# P-MT3620RDB-PS-1-0.net
KiCad netlist of a schematic drawn in Altium Designer
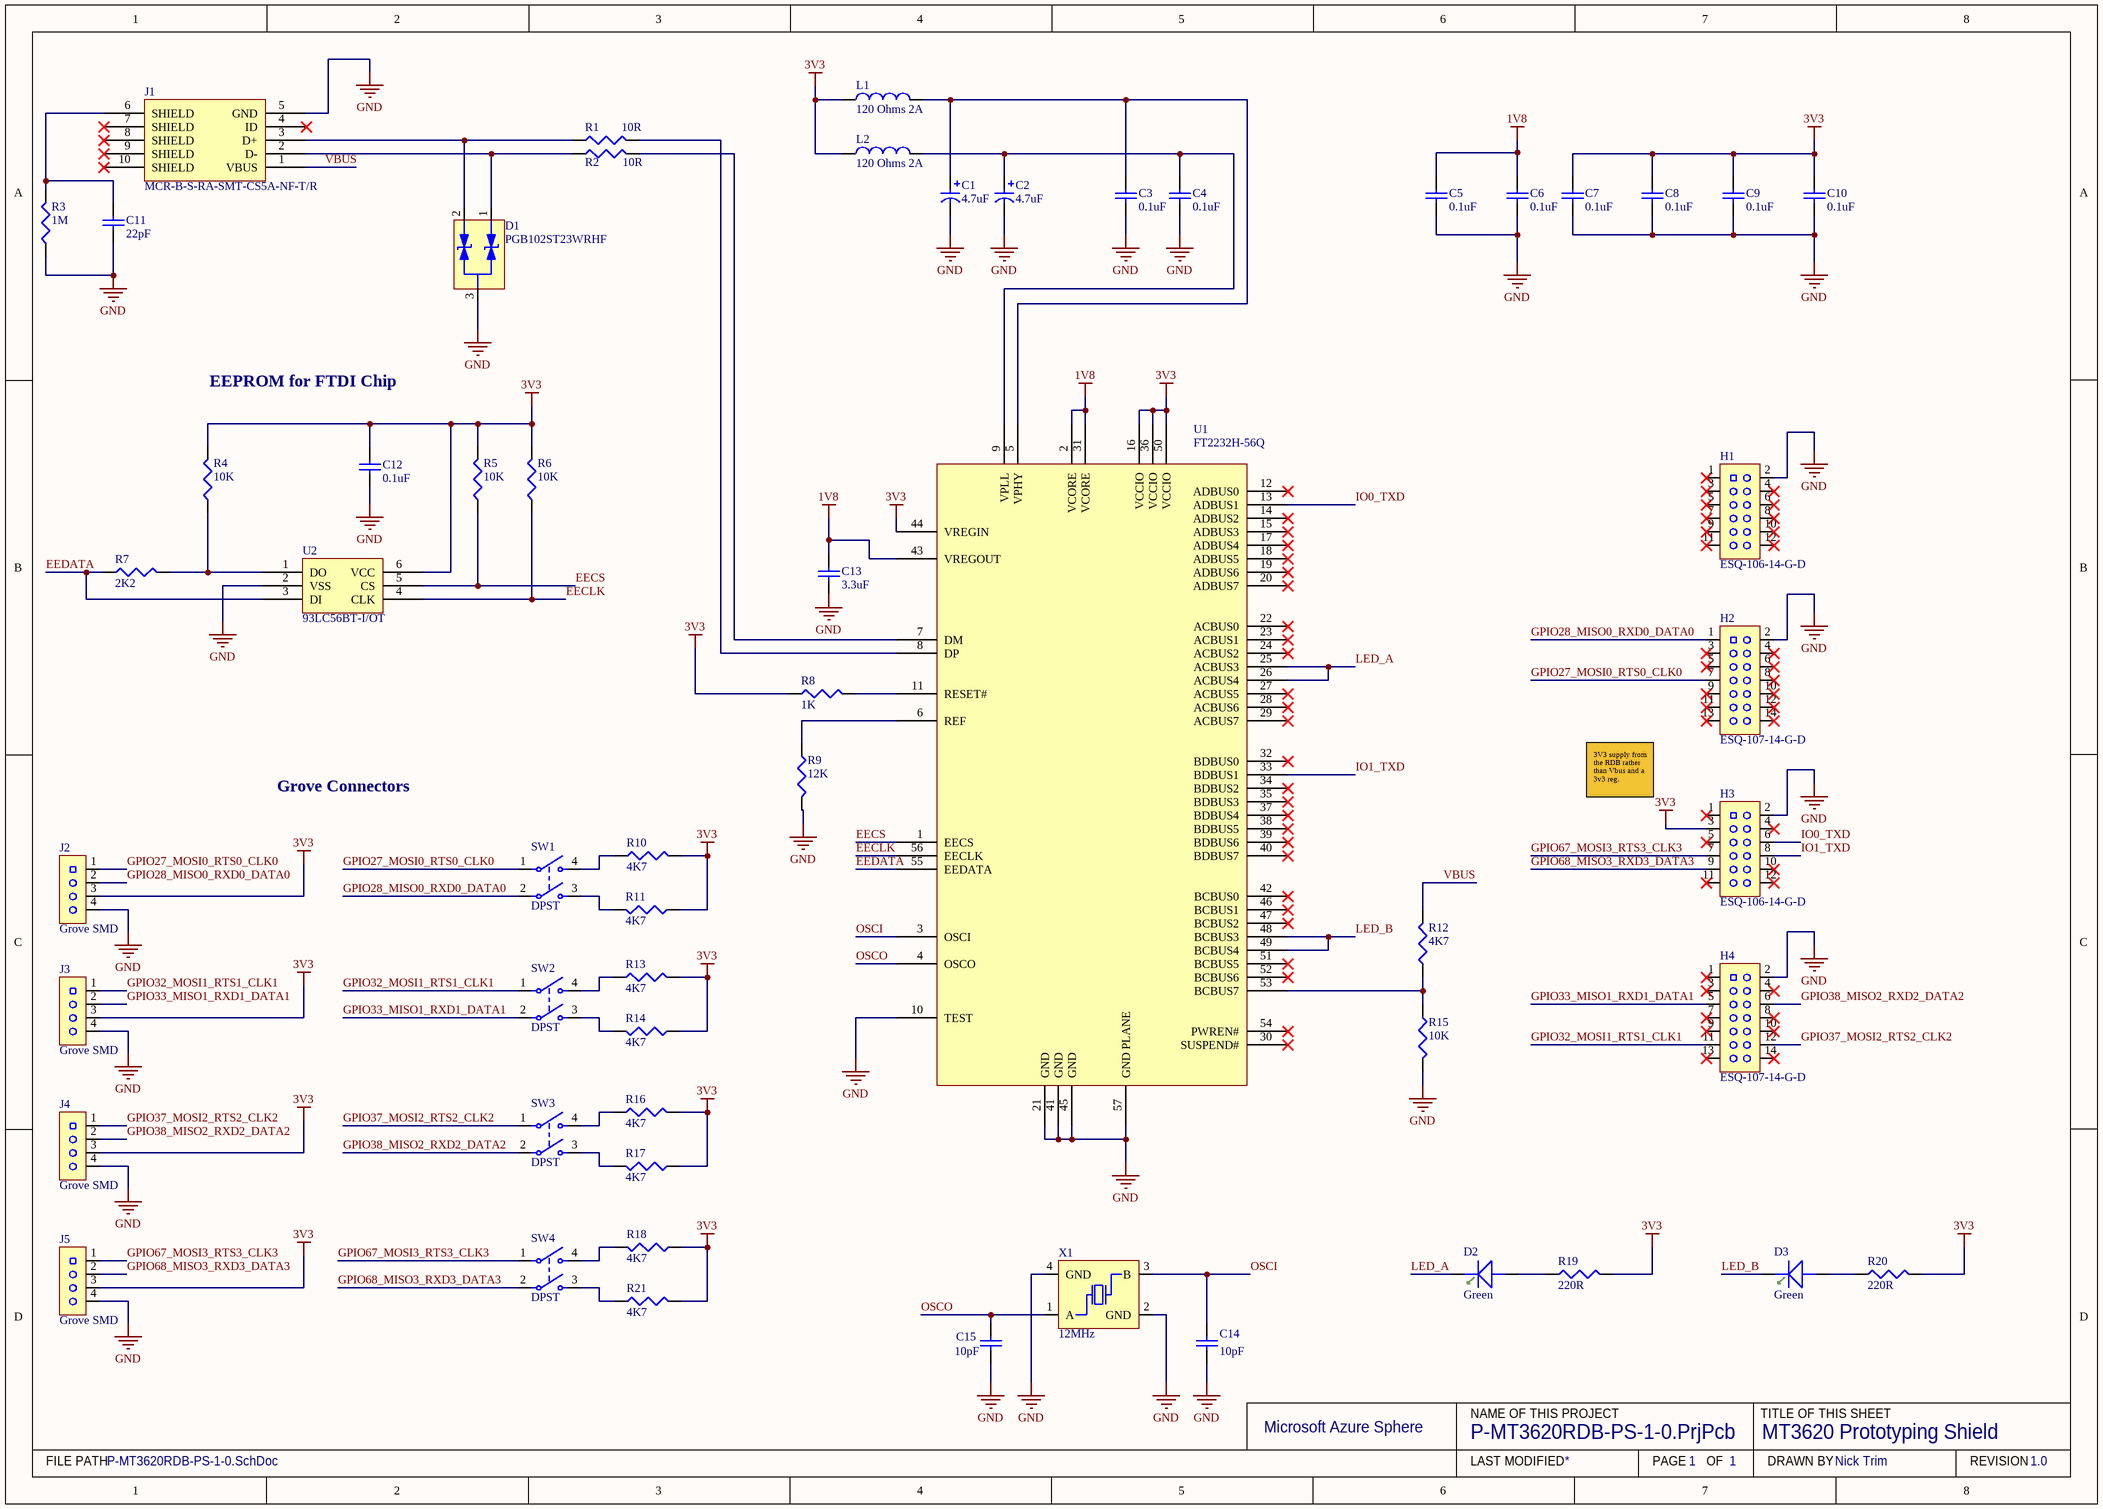
[diagram p0: P-MT3620RDB-PS-1-0.SchDoc]

(export (version "E")
  (design (tool "Eeschema 10.0.6"))
  (components
    (comp (ref "C1")
      (value "4.7uF")
      (footprint "C0603_TANT")
      (fields
        (field (name "MANUFACTURER") "Kyocera AVX")
        (field (name "MANUFACTURER PART NUMBER") "F981A475MMA")
        (field (name "TOLERANCE") "20%")
      )
      (libsource (lib "Prototyping Shield") (part "F981A475MMA"))
    )
    (comp (ref "C2")
      (value "4.7uF")
      (footprint "C0603_TANT")
      (fields
        (field (name "MANUFACTURER") "Kyocera AVX")
        (field (name "MANUFACTURER PART NUMBER") "F981A475MMA")
        (field (name "TOLERANCE") "20%")
      )
      (libsource (lib "Prototyping Shield") (part "F981A475MMA"))
    )
    (comp (ref "C3")
      (value "0.1uF")
      (footprint "C0603")
      (description "CL10 Series 0603 0.1 uF 50 V ±10% Tolerance X7R Multilayer Ceramic Capacitor")
      (fields
        (field (name "MANUFACTURER") "Samsung")
        (field (name "MANUFACTURER PART NUMBER") "CL10B104KB8NNNL")
      )
      (libsource (lib "Prototyping Shield") (part "CL10B104KB8NNNL"))
    )
    (comp (ref "C4")
      (value "0.1uF")
      (footprint "C0603")
      (description "CL10 Series 0603 0.1 uF 50 V ±10% Tolerance X7R Multilayer Ceramic Capacitor")
      (fields
        (field (name "MANUFACTURER") "Samsung")
        (field (name "MANUFACTURER PART NUMBER") "CL10B104KB8NNNL")
      )
      (libsource (lib "Prototyping Shield") (part "CL10B104KB8NNNL"))
    )
    (comp (ref "C5")
      (value "0.1uF")
      (footprint "C0603")
      (description "CL10 Series 0603 0.1 uF 50 V ±10% Tolerance X7R Multilayer Ceramic Capacitor")
      (fields
        (field (name "MANUFACTURER") "Samsung")
        (field (name "MANUFACTURER PART NUMBER") "CL10B104KB8NNNL")
      )
      (libsource (lib "Prototyping Shield") (part "CL10B104KB8NNNL"))
    )
    (comp (ref "C6")
      (value "0.1uF")
      (footprint "C0603")
      (description "CL10 Series 0603 0.1 uF 50 V ±10% Tolerance X7R Multilayer Ceramic Capacitor")
      (fields
        (field (name "MANUFACTURER") "Samsung")
        (field (name "MANUFACTURER PART NUMBER") "CL10B104KB8NNNL")
      )
      (libsource (lib "Prototyping Shield") (part "CL10B104KB8NNNL"))
    )
    (comp (ref "C7")
      (value "0.1uF")
      (footprint "C0603")
      (description "CL10 Series 0603 0.1 uF 50 V ±10% Tolerance X7R Multilayer Ceramic Capacitor")
      (fields
        (field (name "MANUFACTURER") "Samsung")
        (field (name "MANUFACTURER PART NUMBER") "CL10B104KB8NNNL")
      )
      (libsource (lib "Prototyping Shield") (part "CL10B104KB8NNNL"))
    )
    (comp (ref "C8")
      (value "0.1uF")
      (footprint "C0603")
      (description "CL10 Series 0603 0.1 uF 50 V ±10% Tolerance X7R Multilayer Ceramic Capacitor")
      (fields
        (field (name "MANUFACTURER") "Samsung")
        (field (name "MANUFACTURER PART NUMBER") "CL10B104KB8NNNL")
      )
      (libsource (lib "Prototyping Shield") (part "CL10B104KB8NNNL"))
    )
    (comp (ref "C9")
      (value "0.1uF")
      (footprint "C0603")
      (description "CL10 Series 0603 0.1 uF 50 V ±10% Tolerance X7R Multilayer Ceramic Capacitor")
      (fields
        (field (name "MANUFACTURER") "Samsung")
        (field (name "MANUFACTURER PART NUMBER") "CL10B104KB8NNNL")
      )
      (libsource (lib "Prototyping Shield") (part "CL10B104KB8NNNL"))
    )
    (comp (ref "C10")
      (value "0.1uF")
      (footprint "C0603")
      (description "CL10 Series 0603 0.1 uF 50 V ±10% Tolerance X7R Multilayer Ceramic Capacitor")
      (fields
        (field (name "MANUFACTURER") "Samsung")
        (field (name "MANUFACTURER PART NUMBER") "CL10B104KB8NNNL")
      )
      (libsource (lib "Schlib1") (part "CL10B104KB8NNNL"))
    )
    (comp (ref "C11")
      (value "22pF")
      (footprint "C0603")
      (description "Cap Ceramic 22pF 50VDC C0G 5% SMD 0603 Paper T/R")
      (fields
        (field (name "MANUFACTURER") "Yageo")
        (field (name "MANUFACTURER PART NUMBER") "CC0603JRNPO9BN220")
      )
      (libsource (lib "Prototyping Shield") (part "CC0603JRNPO9BN220"))
    )
    (comp (ref "C12")
      (value "0.1uF")
      (footprint "C0603")
      (description "CL10 Series 0603 0.1 uF 50 V ±10% Tolerance X7R Multilayer Ceramic Capacitor")
      (fields
        (field (name "MANUFACTURER") "Samsung")
        (field (name "MANUFACTURER PART NUMBER") "CL10B104KB8NNNL")
      )
      (libsource (lib "Prototyping Shield") (part "CL10B104KB8NNNL"))
    )
    (comp (ref "C13")
      (value "3.3uF")
      (footprint "C0603")
      (description "CAP CER 3.3UF 10V X5R 0603")
      (fields
        (field (name "MANUFACTURER") "Samsung")
        (field (name "MANUFACTURER PART NUMBER") "CL10A335KP8NNNC")
      )
      (libsource (lib "Prototyping Shield") (part "CL10A335KP8NNNC"))
    )
    (comp (ref "C14")
      (value "10pF")
      (footprint "C0603")
      (description "Cap Cer 10PF 100V Npo 0603")
      (fields
        (field (name "MANUFACTURER") "Yageo")
        (field (name "MANUFACTURER PART NUMBER") "CC0603FRNPO0BN100")
      )
      (libsource (lib "Prototyping Shield") (part "CC0603FRNPO0BN100"))
    )
    (comp (ref "C15")
      (value "10pF")
      (footprint "C0603")
      (description "Cap Cer 10PF 100V Npo 0603")
      (fields
        (field (name "MANUFACTURER") "Yageo")
        (field (name "MANUFACTURER PART NUMBER") "CC0603FRNPO0BN100")
      )
      (libsource (lib "Prototyping Shield") (part "CC0603FRNPO0BN100"))
    )
    (comp (ref "D1")
      (value "PGB102ST23WRHF")
      (footprint "SOT95P245X110-3N")
      (description "Tvs Diode 24V 150V SOT23-3")
      (fields (field (name "MANUFACTURER") "Littelfuse"))
      (libsource (lib "Schlib1") (part "PGB102ST23WRHF"))
    )
    (comp (ref "D2")
      (value "Green")
      (footprint "Rohm SML-D12 Green")
      (description "ROHM - SML-D12P8WT86 - LED, EXCELED, Green, SMD, 0603, 20 mA, 2.2 V, 560 nm")
      (fields (field (name "MANUFACTURER") "Rohm") (field (name "MANUFACTURER PART NUMBER") "SML-D12P8WT86"))
      (libsource (lib "Prototyping Shield") (part "SML-D12P8WT86"))
    )
    (comp (ref "D3")
      (value "Green")
      (footprint "Rohm SML-D12 Green")
      (description "ROHM - SML-D12P8WT86 - LED, EXCELED, Green, SMD, 0603, 20 mA, 2.2 V, 560 nm")
      (fields (field (name "MANUFACTURER") "Rohm") (field (name "MANUFACTURER PART NUMBER") "SML-D12P8WT86"))
      (libsource (lib "Prototyping Shield") (part "SML-D12P8WT86"))
    )
    (comp (ref "H1")
      (value "ESQ-106-14-G-D")
      (footprint "ESQ-106")
      (description "Conn Elevated Socket SKT 12 POS 2.54mm Solder ST Thru-Hole Tube")
      (fields (field (name "MANUFACTURER") "Samtec"))
      (libsource (lib "Schlib1") (part "ESQ-106-14-G-D"))
    )
    (comp (ref "H2")
      (value "ESQ-107-14-G-D")
      (footprint "ESQ-107")
      (fields (field (name "MANUFACTURER") "Samtec"))
      (libsource (lib "Schlib1") (part "ESQ-107-14-G-D"))
    )
    (comp (ref "H3")
      (value "ESQ-106-14-G-D")
      (footprint "ESQ-106")
      (description "Conn Elevated Socket SKT 12 POS 2.54mm Solder ST Thru-Hole Tube")
      (fields (field (name "MANUFACTURER") "Samtec"))
      (libsource (lib "Schlib1") (part "ESQ-106-14-G-D"))
    )
    (comp (ref "H4")
      (value "ESQ-107-14-G-D")
      (footprint "ESQ-107")
      (fields (field (name "MANUFACTURER") "Samtec"))
      (libsource (lib "Schlib1") (part "ESQ-107-14-G-D"))
    )
    (comp (ref "J1")
      (value "MCR-B-S-RA-SMT-CS5A-NF-T/R")
      (footprint "MCR-B-S-RA-SMT-CS5-T/R")
      (fields (field (name "MANUFACTURER") "Adam Equipment"))
      (libsource (lib "Prototyping Shield") (part "MCR-B-S-RA-SMT-CS5A-NF-T/R"))
    )
    (comp (ref "J2")
      (value "Grove SMD")
      (footprint "Grove way SMD")
      (fields
        (field (name "MANUFACTURER") "Seeed Studio")
        (field (name "MANUFACTURER PART NUMBER") "114020163")
      )
      (libsource (lib "Prototyping Shield") (part "114020163"))
    )
    (comp (ref "J3")
      (value "Grove SMD")
      (footprint "Grove way SMD")
      (fields
        (field (name "MANUFACTURER") "Seeed Studio")
        (field (name "MANUFACTURER PART NUMBER") "114020163")
      )
      (libsource (lib "Prototyping Shield") (part "114020163"))
    )
    (comp (ref "J4")
      (value "Grove SMD")
      (footprint "Grove way SMD")
      (fields
        (field (name "MANUFACTURER") "Seeed Studio")
        (field (name "MANUFACTURER PART NUMBER") "114020163")
      )
      (libsource (lib "Prototyping Shield") (part "114020163"))
    )
    (comp (ref "J5")
      (value "Grove SMD")
      (footprint "Grove way SMD")
      (fields
        (field (name "MANUFACTURER") "Seeed Studio")
        (field (name "MANUFACTURER PART NUMBER") "114020163")
      )
      (libsource (lib "Prototyping Shield") (part "114020163"))
    )
    (comp (ref "L1")
      (value "120 Ohms 2A")
      (footprint "0603 IND")
      (description "MURATA - BLM18PG121SN1D - FERRITE, BEAD, 0603, 0.05OHM, 2A")
      (fields
        (field (name "MANUFACTURER") "Murata")
        (field (name "MANUFACTURER PART NUMBER") "BLM18PG121SN1D")
      )
      (libsource (lib "Prototyping Shield") (part "BLM18PG121SN1D"))
    )
    (comp (ref "L2")
      (value "120 Ohms 2A")
      (footprint "0603 IND")
      (description "MURATA - BLM18PG121SN1D - FERRITE, BEAD, 0603, 0.05OHM, 2A")
      (fields
        (field (name "MANUFACTURER") "Murata")
        (field (name "MANUFACTURER PART NUMBER") "BLM18PG121SN1D")
      )
      (libsource (lib "Prototyping Shield") (part "BLM18PG121SN1D"))
    )
    (comp (ref "R1")
      (value "10R")
      (footprint "R0603")
      (description "YAGEO (PHYCOMP) - RC0603FR-0710RL - RES, THICK FILM, 10R, 1%, 0.1W, 0603")
      (fields
        (field (name "MANUFACTURER") "Yageo")
        (field (name "MANUFACTURER PART NUMBER") "RC0603FR-0710RL")
      )
      (libsource (lib "Schlib1") (part "RC0603FR-0710RL"))
    )
    (comp (ref "R2")
      (value "10R")
      (footprint "R0603")
      (description "YAGEO (PHYCOMP) - RC0603FR-0710RL - RES, THICK FILM, 10R, 1%, 0.1W, 0603")
      (fields
        (field (name "MANUFACTURER") "Yageo")
        (field (name "MANUFACTURER PART NUMBER") "RC0603FR-0710RL")
      )
      (libsource (lib "Schlib1") (part "RC0603FR-0710RL"))
    )
    (comp (ref "R3")
      (value "1M")
      (footprint "R0603")
      (description "RES SMD 1M OHM 1% 1/10W 0603")
      (fields
        (field (name "MANUFACTURER") "Yageo")
        (field (name "MANUFACTURER PART NUMBER") "AC0603FR-071ML")
      )
      (libsource (lib "Prototyping Shield") (part "AC0603FR-071ML"))
    )
    (comp (ref "R4")
      (value "10K")
      (footprint "R0603")
      (description "Res General Purpose Thick Film 0603 10K Ohm 1% 1/10W ±100ppm/°C Molded SMD Paper T/R")
      (fields
        (field (name "MANUFACTURER") "Yageo")
        (field (name "MANUFACTURER PART NUMBER") "RC0603FR-0710KL")
      )
      (libsource (lib "Prototyping Shield") (part "RC0603FR-0710KL"))
    )
    (comp (ref "R5")
      (value "10K")
      (footprint "R0603")
      (description "Res General Purpose Thick Film 0603 10K Ohm 1% 1/10W ±100ppm/°C Molded SMD Paper T/R")
      (fields
        (field (name "MANUFACTURER") "Yageo")
        (field (name "MANUFACTURER PART NUMBER") "RC0603FR-0710KL")
      )
      (libsource (lib "Prototyping Shield") (part "RC0603FR-0710KL"))
    )
    (comp (ref "R6")
      (value "10K")
      (footprint "R0603")
      (description "Res General Purpose Thick Film 0603 10K Ohm 1% 1/10W ±100ppm/°C Molded SMD Paper T/R")
      (fields
        (field (name "MANUFACTURER") "Yageo")
        (field (name "MANUFACTURER PART NUMBER") "RC0603FR-0710KL")
      )
      (libsource (lib "Prototyping Shield") (part "RC0603FR-0710KL"))
    )
    (comp (ref "R7")
      (value "2K2")
      (footprint "R0603")
      (description "YAGEO - RC0603FR-072K2L.. - RES, THICK FILM, 2K2, 1%, 0.1W, 0603")
      (fields
        (field (name "MANUFACTURER") "Yageo")
        (field (name "MANUFACTURER PART NUMBER") "RC0603FR-072K2L")
      )
      (libsource (lib "Prototyping Shield") (part "RC0603FR-072K2L"))
    )
    (comp (ref "R8")
      (value "1K")
      (footprint "R0603")
      (description "RES SMD 1K OHM 1% 1/10W 0603")
      (fields
        (field (name "MANUFACTURER") "Yageo")
        (field (name "MANUFACTURER PART NUMBER") "RC0603FR-071KL")
      )
      (libsource (lib "Prototyping Shield") (part "RC0603FR-071KL"))
    )
    (comp (ref "R9")
      (value "12K")
      (footprint "R0603")
      (fields
        (field (name "MANUFACTURER") "Yageo")
        (field (name "MANUFACTURER PART NUMBER") "RC0603FR-0712KL")
        (field (name "TOLERANCE") "1%")
      )
      (libsource (lib "Prototyping Shield") (part "RC0603FR-0712KL"))
    )
    (comp (ref "R10")
      (value "4K7")
      (footprint "R0603")
      (description "RES SMD 4.7K OHM 1% 1/10W 0603")
      (fields
        (field (name "MANUFACTURER") "Yageo")
        (field (name "MANUFACTURER PART NUMBER") "RC0603FR-074K7L")
      )
      (libsource (lib "Prototyping Shield") (part "RC0603FR-074K7L"))
    )
    (comp (ref "R11")
      (value "4K7")
      (footprint "R0603")
      (description "RES SMD 4.7K OHM 1% 1/10W 0603")
      (fields
        (field (name "MANUFACTURER") "Yageo")
        (field (name "MANUFACTURER PART NUMBER") "RC0603FR-074K7L")
      )
      (libsource (lib "Prototyping Shield") (part "RC0603FR-074K7L"))
    )
    (comp (ref "R12")
      (value "4K7")
      (footprint "R0603")
      (description "RES SMD 4.7K OHM 1% 1/10W 0603")
      (fields
        (field (name "MANUFACTURER") "Yageo")
        (field (name "MANUFACTURER PART NUMBER") "RC0603FR-074K7L")
      )
      (libsource (lib "Schlib1") (part "RC0603FR-074K7L"))
    )
    (comp (ref "R13")
      (value "4K7")
      (footprint "R0603")
      (description "RES SMD 4.7K OHM 1% 1/10W 0603")
      (fields
        (field (name "MANUFACTURER") "Yageo")
        (field (name "MANUFACTURER PART NUMBER") "RC0603FR-074K7L")
      )
      (libsource (lib "Prototyping Shield") (part "RC0603FR-074K7L"))
    )
    (comp (ref "R14")
      (value "4K7")
      (footprint "R0603")
      (description "RES SMD 4.7K OHM 1% 1/10W 0603")
      (fields
        (field (name "MANUFACTURER") "Yageo")
        (field (name "MANUFACTURER PART NUMBER") "RC0603FR-074K7L")
      )
      (libsource (lib "Prototyping Shield") (part "RC0603FR-074K7L"))
    )
    (comp (ref "R15")
      (value "10K")
      (footprint "R0603")
      (description "Res General Purpose Thick Film 0603 10K Ohm 1% 1/10W ±100ppm/°C Molded SMD Paper T/R")
      (fields
        (field (name "MANUFACTURER") "Yageo")
        (field (name "MANUFACTURER PART NUMBER") "RC0603FR-0710KL")
      )
      (libsource (lib "Schlib1") (part "RC0603FR-0710KL"))
    )
    (comp (ref "R16")
      (value "4K7")
      (footprint "R0603")
      (description "RES SMD 4.7K OHM 1% 1/10W 0603")
      (fields
        (field (name "MANUFACTURER") "Yageo")
        (field (name "MANUFACTURER PART NUMBER") "RC0603FR-074K7L")
      )
      (libsource (lib "Prototyping Shield") (part "RC0603FR-074K7L"))
    )
    (comp (ref "R17")
      (value "4K7")
      (footprint "R0603")
      (description "RES SMD 4.7K OHM 1% 1/10W 0603")
      (fields
        (field (name "MANUFACTURER") "Yageo")
        (field (name "MANUFACTURER PART NUMBER") "RC0603FR-074K7L")
      )
      (libsource (lib "Prototyping Shield") (part "RC0603FR-074K7L"))
    )
    (comp (ref "R18")
      (value "4K7")
      (footprint "R0603")
      (description "RES SMD 4.7K OHM 1% 1/10W 0603")
      (fields
        (field (name "MANUFACTURER") "Yageo")
        (field (name "MANUFACTURER PART NUMBER") "RC0603FR-074K7L")
      )
      (libsource (lib "Prototyping Shield") (part "RC0603FR-074K7L"))
    )
    (comp (ref "R19")
      (value "220R")
      (footprint "R0603")
      (fields
        (field (name "MANUFACTURER") "Yageo")
        (field (name "MANUFACTURER PART NUMBER") "RC0603FR-07220RL")
        (field (name "TOLERANCE") "1%")
      )
      (libsource (lib "Prototyping Shield") (part "RC0603FR-07220RL"))
    )
    (comp (ref "R20")
      (value "220R")
      (footprint "R0603")
      (fields
        (field (name "MANUFACTURER") "Yageo")
        (field (name "MANUFACTURER PART NUMBER") "RC0603FR-07220RL")
        (field (name "TOLERANCE") "1%")
      )
      (libsource (lib "Prototyping Shield") (part "RC0603FR-07220RL"))
    )
    (comp (ref "R21")
      (value "4K7")
      (footprint "R0603")
      (description "RES SMD 4.7K OHM 1% 1/10W 0603")
      (fields
        (field (name "MANUFACTURER") "Yageo")
        (field (name "MANUFACTURER PART NUMBER") "RC0603FR-074K7L")
      )
      (libsource (lib "Prototyping Shield") (part "RC0603FR-074K7L"))
    )
    (comp (ref "SW1")
      (value "DPST")
      (footprint "204-211ST")
      (description "SWITCH SLIDE DIP DPST 50MA 24V")
      (fields (field (name "MANUFACTURER") "CTS") (field (name "MANUFACTURER PART NUMBER") "204-211ST"))
      (libsource (lib "Prototyping Shield") (part "204-211ST"))
    )
    (comp (ref "SW2")
      (value "DPST")
      (footprint "204-211ST")
      (description "SWITCH SLIDE DIP DPST 50MA 24V")
      (fields (field (name "MANUFACTURER") "CTS") (field (name "MANUFACTURER PART NUMBER") "204-211ST"))
      (libsource (lib "Prototyping Shield") (part "204-211ST"))
    )
    (comp (ref "SW3")
      (value "DPST")
      (footprint "204-211ST")
      (description "SWITCH SLIDE DIP DPST 50MA 24V")
      (fields (field (name "MANUFACTURER") "CTS") (field (name "MANUFACTURER PART NUMBER") "204-211ST"))
      (libsource (lib "Prototyping Shield") (part "204-211ST"))
    )
    (comp (ref "SW4")
      (value "DPST")
      (footprint "204-211ST")
      (description "SWITCH SLIDE DIP DPST 50MA 24V")
      (fields (field (name "MANUFACTURER") "CTS") (field (name "MANUFACTURER PART NUMBER") "204-211ST"))
      (libsource (lib "Prototyping Shield") (part "204-211ST"))
    )
    (comp (ref "U1")
      (value "FT2232H-56Q")
      (footprint "FT2232H-56Q")
      (description "IC DUAL USB TO UART/FIFO 56VQFN")
      (fields
        (field (name "MANUFACTURER") "FTDI")
        (field (name "MANUFACTURER PART NUMBER") "FT2232H-56Q-TRAY")
      )
      (libsource (lib "Prototyping Shield") (part "FT2232H-56Q-TRAY"))
    )
    (comp (ref "U2")
      (value "93LC56BT-I/OT")
      (footprint "SOT23-93C56B")
      (description "MICROCHIP - 93LC56BT-I/OT. - 2K, 128 X 16, SERIAL EE, IND ROHS COMPLIANT: YES")
      (fields (field (name "MANUFACTURER") "Microchip"))
      (libsource (lib "Prototyping Shield") (part "93LC56BT-I/OT"))
    )
    (comp (ref "X1")
      (value "12MHz")
      (footprint "TXC8Z")
      (description "Crystal 12MHz ±30ppm (Tol) ±30ppm (Stability) 18pF FUND 150Ohm 4-Pin SMD T/R")
      (fields (field (name "MANUFACTURER") "TXC") (field (name "MANUFACTURER PART NUMBER") "8Z-12.000MAAJ-T"))
      (libsource (lib "Prototyping Shield") (part "8Z-12.000MAAJ-T"))
    )
  )
  (nets
    (net (code "1") (name "/EECLK") (class "Default")
      (node (ref "R6") (pin "1") (pinfunction "1_1") (pintype "passive"))
      (node (ref "U1") (pin "56") (pinfunction "EECLK_56") (pintype "passive"))
      (node (ref "U2") (pin "4") (pinfunction "CLK_4") (pintype "passive"))
    )
    (net (code "2") (name "/EECS") (class "Default")
      (node (ref "R5") (pin "1") (pinfunction "1_1") (pintype "passive"))
      (node (ref "U1") (pin "1") (pinfunction "EECS_1") (pintype "passive"))
      (node (ref "U2") (pin "5") (pinfunction "CS_5") (pintype "passive"))
    )
    (net (code "3") (name "/EEDATA") (class "Default")
      (node (ref "R7") (pin "1") (pinfunction "1_1") (pintype "passive"))
      (node (ref "U1") (pin "55") (pinfunction "EEDATA_55") (pintype "passive"))
      (node (ref "U2") (pin "3") (pinfunction "DI_3") (pintype "passive"))
    )
    (net (code "4") (name "/GPIO27_MOSI0_RTS0_CLK0") (class "Default")
      (node (ref "H2") (pin "7") (pintype "passive"))
      (node (ref "J2") (pin "1") (pintype "passive"))
      (node (ref "SW1") (pin "1") (pintype "passive"))
    )
    (net (code "5") (name "/GPIO28_MISO0_RXD0_DATA0") (class "Default")
      (node (ref "H2") (pin "1") (pintype "passive"))
      (node (ref "J2") (pin "2") (pintype "passive"))
      (node (ref "SW1") (pin "2") (pintype "passive"))
    )
    (net (code "6") (name "/GPIO32_MOSI1_RTS1_CLK1") (class "Default")
      (node (ref "H4") (pin "11") (pintype "passive"))
      (node (ref "J3") (pin "1") (pintype "passive"))
      (node (ref "SW2") (pin "1") (pintype "passive"))
    )
    (net (code "7") (name "/GPIO33_MISO1_RXD1_DATA1") (class "Default")
      (node (ref "H4") (pin "5") (pintype "passive"))
      (node (ref "J3") (pin "2") (pintype "passive"))
      (node (ref "SW2") (pin "2") (pintype "passive"))
    )
    (net (code "8") (name "/GPIO37_MOSI2_RTS2_CLK2") (class "Default")
      (node (ref "H4") (pin "12") (pintype "passive"))
      (node (ref "J4") (pin "1") (pintype "passive"))
      (node (ref "SW3") (pin "1") (pintype "passive"))
    )
    (net (code "9") (name "/GPIO38_MISO2_RXD2_DATA2") (class "Default")
      (node (ref "H4") (pin "6") (pintype "passive"))
      (node (ref "J4") (pin "2") (pintype "passive"))
      (node (ref "SW3") (pin "2") (pintype "passive"))
    )
    (net (code "10") (name "/GPIO67_MOSI3_RTS3_CLK3") (class "Default")
      (node (ref "H3") (pin "7") (pintype "passive"))
      (node (ref "J5") (pin "1") (pintype "passive"))
      (node (ref "SW4") (pin "1") (pintype "passive"))
    )
    (net (code "11") (name "/GPIO68_MISO3_RXD3_DATA3") (class "Default")
      (node (ref "H3") (pin "9") (pintype "passive"))
      (node (ref "J5") (pin "2") (pintype "passive"))
      (node (ref "SW4") (pin "2") (pintype "passive"))
    )
    (net (code "12") (name "/IO0_TXD") (class "Default")
      (node (ref "H3") (pin "6") (pintype "passive"))
      (node (ref "U1") (pin "13") (pinfunction "ADBUS1_13") (pintype "passive"))
    )
    (net (code "13") (name "/IO1_TXD") (class "Default")
      (node (ref "H3") (pin "8") (pintype "passive"))
      (node (ref "U1") (pin "33") (pinfunction "BDBUS1_33") (pintype "passive"))
    )
    (net (code "14") (name "/LED_A") (class "Default")
      (node (ref "D2") (pin "1") (pinfunction "1_1") (pintype "passive"))
      (node (ref "U1") (pin "25") (pinfunction "ACBUS3_25") (pintype "passive"))
      (node (ref "U1") (pin "26") (pinfunction "ACBUS4_26") (pintype "passive"))
    )
    (net (code "15") (name "/LED_B") (class "Default")
      (node (ref "D3") (pin "1") (pinfunction "1_1") (pintype "passive"))
      (node (ref "U1") (pin "48") (pinfunction "BCBUS3_48") (pintype "passive"))
      (node (ref "U1") (pin "49") (pinfunction "BCBUS4_49") (pintype "passive"))
    )
    (net (code "16") (name "/OSCI") (class "Default")
      (node (ref "C14") (pin "1") (pinfunction "1_1") (pintype "passive"))
      (node (ref "U1") (pin "3") (pinfunction "OSCI_3") (pintype "passive"))
      (node (ref "X1") (pin "3") (pinfunction "B_3") (pintype "passive"))
    )
    (net (code "17") (name "/OSCO") (class "Default")
      (node (ref "C15") (pin "1") (pinfunction "1_1") (pintype "passive"))
      (node (ref "U1") (pin "4") (pinfunction "OSCO_4") (pintype "passive"))
      (node (ref "X1") (pin "1") (pinfunction "A_1") (pintype "passive"))
    )
    (net (code "18") (name "/VBUS") (class "Default")
      (node (ref "J1") (pin "1") (pinfunction "VBUS_1") (pintype "passive"))
      (node (ref "R12") (pin "2") (pinfunction "2_2") (pintype "passive"))
    )
    (net (code "19") (name "1V8") (class "Default")
      (node (ref "C13") (pin "2") (pinfunction "2_2") (pintype "passive"))
      (node (ref "C5") (pin "2") (pinfunction "2_2") (pintype "passive"))
      (node (ref "C6") (pin "2") (pinfunction "2_2") (pintype "passive"))
      (node (ref "U1") (pin "2") (pinfunction "VCORE_2") (pintype "passive"))
      (node (ref "U1") (pin "31") (pinfunction "VCORE_31") (pintype "passive"))
      (node (ref "U1") (pin "43") (pinfunction "VREGOUT_43") (pintype "passive"))
    )
    (net (code "20") (name "3V3") (class "Default")
      (node (ref "C10") (pin "2") (pinfunction "2_2") (pintype "passive"))
      (node (ref "C12") (pin "2") (pinfunction "2_2") (pintype "passive"))
      (node (ref "C7") (pin "1") (pinfunction "1_1") (pintype "passive"))
      (node (ref "C8") (pin "2") (pinfunction "2_2") (pintype "passive"))
      (node (ref "C9") (pin "2") (pinfunction "2_2") (pintype "passive"))
      (node (ref "H3") (pin "3") (pintype "passive"))
      (node (ref "J2") (pin "3") (pintype "passive"))
      (node (ref "J3") (pin "3") (pintype "passive"))
      (node (ref "J4") (pin "3") (pintype "passive"))
      (node (ref "J5") (pin "3") (pintype "passive"))
      (node (ref "L1") (pin "1") (pinfunction "1_1") (pintype "passive"))
      (node (ref "L2") (pin "1") (pinfunction "1_1") (pintype "passive"))
      (node (ref "R10") (pin "2") (pinfunction "2_2") (pintype "passive"))
      (node (ref "R11") (pin "1") (pinfunction "1_1") (pintype "passive"))
      (node (ref "R13") (pin "2") (pinfunction "2_2") (pintype "passive"))
      (node (ref "R14") (pin "1") (pinfunction "1_1") (pintype "passive"))
      (node (ref "R16") (pin "2") (pinfunction "2_2") (pintype "passive"))
      (node (ref "R17") (pin "1") (pinfunction "1_1") (pintype "passive"))
      (node (ref "R18") (pin "1") (pinfunction "1_1") (pintype "passive"))
      (node (ref "R19") (pin "2") (pinfunction "2_2") (pintype "passive"))
      (node (ref "R20") (pin "2") (pinfunction "2_2") (pintype "passive"))
      (node (ref "R21") (pin "2") (pinfunction "2_2") (pintype "passive"))
      (node (ref "R4") (pin "2") (pinfunction "2_2") (pintype "passive"))
      (node (ref "R5") (pin "2") (pinfunction "2_2") (pintype "passive"))
      (node (ref "R6") (pin "2") (pinfunction "2_2") (pintype "passive"))
      (node (ref "R8") (pin "1") (pinfunction "1_1") (pintype "passive"))
      (node (ref "U1") (pin "16") (pinfunction "VCCIO_16") (pintype "passive"))
      (node (ref "U1") (pin "36") (pinfunction "VCCIO_36") (pintype "passive"))
      (node (ref "U1") (pin "44") (pinfunction "VREGIN_44") (pintype "passive"))
      (node (ref "U1") (pin "50") (pinfunction "VCCIO_50") (pintype "passive"))
      (node (ref "U2") (pin "6") (pinfunction "VCC_6") (pintype "passive"))
    )
    (net (code "21") (name "GND") (class "Default")
      (node (ref "C1") (pin "2") (pinfunction "2_2") (pintype "passive"))
      (node (ref "C10") (pin "1") (pinfunction "1_1") (pintype "passive"))
      (node (ref "C11") (pin "1") (pinfunction "1_1") (pintype "passive"))
      (node (ref "C12") (pin "1") (pinfunction "1_1") (pintype "passive"))
      (node (ref "C13") (pin "1") (pinfunction "1_1") (pintype "passive"))
      (node (ref "C14") (pin "2") (pinfunction "2_2") (pintype "passive"))
      (node (ref "C15") (pin "2") (pinfunction "2_2") (pintype "passive"))
      (node (ref "C2") (pin "2") (pinfunction "2_2") (pintype "passive"))
      (node (ref "C3") (pin "2") (pinfunction "2_2") (pintype "passive"))
      (node (ref "C4") (pin "1") (pinfunction "1_1") (pintype "passive"))
      (node (ref "C5") (pin "1") (pinfunction "1_1") (pintype "passive"))
      (node (ref "C6") (pin "1") (pinfunction "1_1") (pintype "passive"))
      (node (ref "C7") (pin "2") (pinfunction "2_2") (pintype "passive"))
      (node (ref "C8") (pin "1") (pinfunction "1_1") (pintype "passive"))
      (node (ref "C9") (pin "1") (pinfunction "1_1") (pintype "passive"))
      (node (ref "D1") (pin "3") (pinfunction "3_3") (pintype "passive"))
      (node (ref "H1") (pin "2") (pintype "passive"))
      (node (ref "H2") (pin "2") (pintype "passive"))
      (node (ref "H3") (pin "2") (pintype "passive"))
      (node (ref "H4") (pin "2") (pintype "passive"))
      (node (ref "J1") (pin "5") (pinfunction "GND_5") (pintype "passive"))
      (node (ref "J2") (pin "4") (pintype "passive"))
      (node (ref "J3") (pin "4") (pintype "passive"))
      (node (ref "J4") (pin "4") (pintype "passive"))
      (node (ref "J5") (pin "4") (pintype "passive"))
      (node (ref "R15") (pin "2") (pinfunction "2_2") (pintype "passive"))
      (node (ref "R3") (pin "1") (pinfunction "1_1") (pintype "passive"))
      (node (ref "R9") (pin "2") (pinfunction "2_2") (pintype "passive"))
      (node (ref "U1") (pin "10") (pinfunction "TEST_10") (pintype "passive"))
      (node (ref "U1") (pin "21") (pinfunction "GND_21") (pintype "passive"))
      (node (ref "U1") (pin "41") (pinfunction "GND_41") (pintype "passive"))
      (node (ref "U1") (pin "45") (pinfunction "GND_45") (pintype "passive"))
      (node (ref "U1") (pin "57") (pinfunction "GND_PLANE_57") (pintype "passive"))
      (node (ref "U2") (pin "2") (pinfunction "VSS_2") (pintype "passive"))
      (node (ref "X1") (pin "2") (pinfunction "GND_2") (pintype "passive"))
      (node (ref "X1") (pin "4") (pinfunction "GND_4") (pintype "passive"))
    )
    (net (code "22") (name "Net-(C11-Pad2)") (class "Default")
      (node (ref "C11") (pin "2") (pinfunction "2_2") (pintype "passive"))
      (node (ref "J1") (pin "6") (pinfunction "SHIELD_6") (pintype "passive"))
      (node (ref "R3") (pin "2") (pinfunction "2_2") (pintype "passive"))
    )
    (net (code "23") (name "Net-(D2-Pad2)") (class "Default")
      (node (ref "D2") (pin "2") (pinfunction "2_2") (pintype "passive"))
      (node (ref "R19") (pin "1") (pinfunction "1_1") (pintype "passive"))
    )
    (net (code "24") (name "Net-(D3-Pad2)") (class "Default")
      (node (ref "D3") (pin "2") (pinfunction "2_2") (pintype "passive"))
      (node (ref "R20") (pin "1") (pinfunction "1_1") (pintype "passive"))
    )
    (net (code "25") (name "Net-(J1-D+)") (class "Default")
      (node (ref "D1") (pin "2") (pinfunction "2_2") (pintype "passive"))
      (node (ref "J1") (pin "3") (pinfunction "D+_3") (pintype "passive"))
      (node (ref "R1") (pin "1") (pinfunction "1_1") (pintype "passive"))
    )
    (net (code "26") (name "Net-(J1-D-)") (class "Default")
      (node (ref "D1") (pin "1") (pinfunction "1_1") (pintype "passive"))
      (node (ref "J1") (pin "2") (pinfunction "D-_2") (pintype "passive"))
      (node (ref "R2") (pin "1") (pinfunction "1_1") (pintype "passive"))
    )
    (net (code "27") (name "Net-(R10-Pad1)") (class "Default")
      (node (ref "R10") (pin "1") (pinfunction "1_1") (pintype "passive"))
      (node (ref "SW1") (pin "4") (pintype "passive"))
    )
    (net (code "28") (name "Net-(R11-Pad2)") (class "Default")
      (node (ref "R11") (pin "2") (pinfunction "2_2") (pintype "passive"))
      (node (ref "SW1") (pin "3") (pintype "passive"))
    )
    (net (code "29") (name "Net-(R13-Pad1)") (class "Default")
      (node (ref "R13") (pin "1") (pinfunction "1_1") (pintype "passive"))
      (node (ref "SW2") (pin "4") (pintype "passive"))
    )
    (net (code "30") (name "Net-(R14-Pad2)") (class "Default")
      (node (ref "R14") (pin "2") (pinfunction "2_2") (pintype "passive"))
      (node (ref "SW2") (pin "3") (pintype "passive"))
    )
    (net (code "31") (name "Net-(R16-Pad1)") (class "Default")
      (node (ref "R16") (pin "1") (pinfunction "1_1") (pintype "passive"))
      (node (ref "SW3") (pin "4") (pintype "passive"))
    )
    (net (code "32") (name "Net-(R17-Pad2)") (class "Default")
      (node (ref "R17") (pin "2") (pinfunction "2_2") (pintype "passive"))
      (node (ref "SW3") (pin "3") (pintype "passive"))
    )
    (net (code "33") (name "Net-(R18-Pad2)") (class "Default")
      (node (ref "R18") (pin "2") (pinfunction "2_2") (pintype "passive"))
      (node (ref "SW4") (pin "4") (pintype "passive"))
    )
    (net (code "34") (name "Net-(R21-Pad1)") (class "Default")
      (node (ref "R21") (pin "1") (pinfunction "1_1") (pintype "passive"))
      (node (ref "SW4") (pin "3") (pintype "passive"))
    )
    (net (code "35") (name "Net-(U1-BCBUS7)") (class "Default")
      (node (ref "R12") (pin "1") (pinfunction "1_1") (pintype "passive"))
      (node (ref "R15") (pin "1") (pinfunction "1_1") (pintype "passive"))
      (node (ref "U1") (pin "53") (pinfunction "BCBUS7_53") (pintype "passive"))
    )
    (net (code "36") (name "Net-(U1-DM)") (class "Default")
      (node (ref "R2") (pin "2") (pinfunction "2_2") (pintype "passive"))
      (node (ref "U1") (pin "7") (pinfunction "DM_7") (pintype "passive"))
    )
    (net (code "37") (name "Net-(U1-DP)") (class "Default")
      (node (ref "R1") (pin "2") (pinfunction "2_2") (pintype "passive"))
      (node (ref "U1") (pin "8") (pinfunction "DP_8") (pintype "passive"))
    )
    (net (code "38") (name "Net-(U1-REF)") (class "Default")
      (node (ref "R9") (pin "1") (pinfunction "1_1") (pintype "passive"))
      (node (ref "U1") (pin "6") (pinfunction "REF_6") (pintype "passive"))
    )
    (net (code "39") (name "Net-(U1-RESET#)") (class "Default")
      (node (ref "R8") (pin "2") (pinfunction "2_2") (pintype "passive"))
      (node (ref "U1") (pin "11") (pinfunction "RESET#_11") (pintype "passive"))
    )
    (net (code "40") (name "Net-(U1-VPHY)") (class "Default")
      (node (ref "C1") (pin "1") (pinfunction "1_1") (pintype "passive"))
      (node (ref "C3") (pin "1") (pinfunction "1_1") (pintype "passive"))
      (node (ref "L1") (pin "2") (pinfunction "2_2") (pintype "passive"))
      (node (ref "U1") (pin "5") (pinfunction "VPHY_5") (pintype "passive"))
    )
    (net (code "41") (name "Net-(U1-VPLL)") (class "Default")
      (node (ref "C2") (pin "1") (pinfunction "1_1") (pintype "passive"))
      (node (ref "C4") (pin "2") (pinfunction "2_2") (pintype "passive"))
      (node (ref "L2") (pin "2") (pinfunction "2_2") (pintype "passive"))
      (node (ref "U1") (pin "9") (pinfunction "VPLL_9") (pintype "passive"))
    )
    (net (code "42") (name "Net-(U2-DO)") (class "Default")
      (node (ref "R4") (pin "1") (pinfunction "1_1") (pintype "passive"))
      (node (ref "R7") (pin "2") (pinfunction "2_2") (pintype "passive"))
      (node (ref "U2") (pin "1") (pinfunction "DO_1") (pintype "passive"))
    )
    (net (code "43") (name "unconnected-(H1-Pad1)") (class "Default")
      (node (ref "H1") (pin "1") (pintype "passive+no_connect"))
    )
    (net (code "44") (name "unconnected-(H1-Pad3)") (class "Default")
      (node (ref "H1") (pin "3") (pintype "passive+no_connect"))
    )
    (net (code "45") (name "unconnected-(H1-Pad4)") (class "Default")
      (node (ref "H1") (pin "4") (pintype "passive+no_connect"))
    )
    (net (code "46") (name "unconnected-(H1-Pad5)") (class "Default")
      (node (ref "H1") (pin "5") (pintype "passive+no_connect"))
    )
    (net (code "47") (name "unconnected-(H1-Pad6)") (class "Default")
      (node (ref "H1") (pin "6") (pintype "passive+no_connect"))
    )
    (net (code "48") (name "unconnected-(H1-Pad7)") (class "Default")
      (node (ref "H1") (pin "7") (pintype "passive+no_connect"))
    )
    (net (code "49") (name "unconnected-(H1-Pad8)") (class "Default")
      (node (ref "H1") (pin "8") (pintype "passive+no_connect"))
    )
    (net (code "50") (name "unconnected-(H1-Pad9)") (class "Default")
      (node (ref "H1") (pin "9") (pintype "passive+no_connect"))
    )
    (net (code "51") (name "unconnected-(H1-Pad10)") (class "Default")
      (node (ref "H1") (pin "10") (pintype "passive+no_connect"))
    )
    (net (code "52") (name "unconnected-(H1-Pad11)") (class "Default")
      (node (ref "H1") (pin "11") (pintype "passive+no_connect"))
    )
    (net (code "53") (name "unconnected-(H1-Pad12)") (class "Default")
      (node (ref "H1") (pin "12") (pintype "passive+no_connect"))
    )
    (net (code "54") (name "unconnected-(H2-Pad3)") (class "Default")
      (node (ref "H2") (pin "3") (pintype "passive+no_connect"))
    )
    (net (code "55") (name "unconnected-(H2-Pad4)") (class "Default")
      (node (ref "H2") (pin "4") (pintype "passive+no_connect"))
    )
    (net (code "56") (name "unconnected-(H2-Pad5)") (class "Default")
      (node (ref "H2") (pin "5") (pintype "passive+no_connect"))
    )
    (net (code "57") (name "unconnected-(H2-Pad6)") (class "Default")
      (node (ref "H2") (pin "6") (pintype "passive+no_connect"))
    )
    (net (code "58") (name "unconnected-(H2-Pad8)") (class "Default")
      (node (ref "H2") (pin "8") (pintype "passive+no_connect"))
    )
    (net (code "59") (name "unconnected-(H2-Pad9)") (class "Default")
      (node (ref "H2") (pin "9") (pintype "passive+no_connect"))
    )
    (net (code "60") (name "unconnected-(H2-Pad10)") (class "Default")
      (node (ref "H2") (pin "10") (pintype "passive+no_connect"))
    )
    (net (code "61") (name "unconnected-(H2-Pad11)") (class "Default")
      (node (ref "H2") (pin "11") (pintype "passive+no_connect"))
    )
    (net (code "62") (name "unconnected-(H2-Pad12)") (class "Default")
      (node (ref "H2") (pin "12") (pintype "passive+no_connect"))
    )
    (net (code "63") (name "unconnected-(H2-Pad13)") (class "Default")
      (node (ref "H2") (pin "13") (pintype "passive+no_connect"))
    )
    (net (code "64") (name "unconnected-(H2-Pad14)") (class "Default")
      (node (ref "H2") (pin "14") (pintype "passive+no_connect"))
    )
    (net (code "65") (name "unconnected-(H3-Pad1)") (class "Default")
      (node (ref "H3") (pin "1") (pintype "passive+no_connect"))
    )
    (net (code "66") (name "unconnected-(H3-Pad4)") (class "Default")
      (node (ref "H3") (pin "4") (pintype "passive+no_connect"))
    )
    (net (code "67") (name "unconnected-(H3-Pad5)") (class "Default")
      (node (ref "H3") (pin "5") (pintype "passive+no_connect"))
    )
    (net (code "68") (name "unconnected-(H3-Pad10)") (class "Default")
      (node (ref "H3") (pin "10") (pintype "passive+no_connect"))
    )
    (net (code "69") (name "unconnected-(H3-Pad11)") (class "Default")
      (node (ref "H3") (pin "11") (pintype "passive+no_connect"))
    )
    (net (code "70") (name "unconnected-(H3-Pad12)") (class "Default")
      (node (ref "H3") (pin "12") (pintype "passive+no_connect"))
    )
    (net (code "71") (name "unconnected-(H4-Pad1)") (class "Default")
      (node (ref "H4") (pin "1") (pintype "passive+no_connect"))
    )
    (net (code "72") (name "unconnected-(H4-Pad3)") (class "Default")
      (node (ref "H4") (pin "3") (pintype "passive+no_connect"))
    )
    (net (code "73") (name "unconnected-(H4-Pad4)") (class "Default")
      (node (ref "H4") (pin "4") (pintype "passive+no_connect"))
    )
    (net (code "74") (name "unconnected-(H4-Pad7)") (class "Default")
      (node (ref "H4") (pin "7") (pintype "passive+no_connect"))
    )
    (net (code "75") (name "unconnected-(H4-Pad8)") (class "Default")
      (node (ref "H4") (pin "8") (pintype "passive+no_connect"))
    )
    (net (code "76") (name "unconnected-(H4-Pad9)") (class "Default")
      (node (ref "H4") (pin "9") (pintype "passive+no_connect"))
    )
    (net (code "77") (name "unconnected-(H4-Pad10)") (class "Default")
      (node (ref "H4") (pin "10") (pintype "passive+no_connect"))
    )
    (net (code "78") (name "unconnected-(H4-Pad13)") (class "Default")
      (node (ref "H4") (pin "13") (pintype "passive+no_connect"))
    )
    (net (code "79") (name "unconnected-(H4-Pad14)") (class "Default")
      (node (ref "H4") (pin "14") (pintype "passive+no_connect"))
    )
    (net (code "80") (name "unconnected-(J1-ID-Pad4)") (class "Default")
      (node (ref "J1") (pin "4") (pinfunction "ID_4") (pintype "passive+no_connect"))
    )
    (net (code "81") (name "unconnected-(J1-SHIELD-Pad7)") (class "Default")
      (node (ref "J1") (pin "7") (pinfunction "SHIELD_7") (pintype "passive+no_connect"))
    )
    (net (code "82") (name "unconnected-(J1-SHIELD-Pad8)") (class "Default")
      (node (ref "J1") (pin "8") (pinfunction "SHIELD_8") (pintype "passive+no_connect"))
    )
    (net (code "83") (name "unconnected-(J1-SHIELD-Pad9)") (class "Default")
      (node (ref "J1") (pin "9") (pinfunction "SHIELD_9") (pintype "passive+no_connect"))
    )
    (net (code "84") (name "unconnected-(J1-SHIELD-Pad10)") (class "Default")
      (node (ref "J1") (pin "10") (pinfunction "SHIELD_10") (pintype "passive+no_connect"))
    )
    (net (code "85") (name "unconnected-(U1-ACBUS0-Pad22)") (class "Default")
      (node (ref "U1") (pin "22") (pinfunction "ACBUS0_22") (pintype "passive+no_connect"))
    )
    (net (code "86") (name "unconnected-(U1-ACBUS1-Pad23)") (class "Default")
      (node (ref "U1") (pin "23") (pinfunction "ACBUS1_23") (pintype "passive+no_connect"))
    )
    (net (code "87") (name "unconnected-(U1-ACBUS2-Pad24)") (class "Default")
      (node (ref "U1") (pin "24") (pinfunction "ACBUS2_24") (pintype "passive+no_connect"))
    )
    (net (code "88") (name "unconnected-(U1-ACBUS5-Pad27)") (class "Default")
      (node (ref "U1") (pin "27") (pinfunction "ACBUS5_27") (pintype "passive+no_connect"))
    )
    (net (code "89") (name "unconnected-(U1-ACBUS6-Pad28)") (class "Default")
      (node (ref "U1") (pin "28") (pinfunction "ACBUS6_28") (pintype "passive+no_connect"))
    )
    (net (code "90") (name "unconnected-(U1-ACBUS7-Pad29)") (class "Default")
      (node (ref "U1") (pin "29") (pinfunction "ACBUS7_29") (pintype "passive+no_connect"))
    )
    (net (code "91") (name "unconnected-(U1-ADBUS0-Pad12)") (class "Default")
      (node (ref "U1") (pin "12") (pinfunction "ADBUS0_12") (pintype "passive+no_connect"))
    )
    (net (code "92") (name "unconnected-(U1-ADBUS2-Pad14)") (class "Default")
      (node (ref "U1") (pin "14") (pinfunction "ADBUS2_14") (pintype "passive+no_connect"))
    )
    (net (code "93") (name "unconnected-(U1-ADBUS3-Pad15)") (class "Default")
      (node (ref "U1") (pin "15") (pinfunction "ADBUS3_15") (pintype "passive+no_connect"))
    )
    (net (code "94") (name "unconnected-(U1-ADBUS4-Pad17)") (class "Default")
      (node (ref "U1") (pin "17") (pinfunction "ADBUS4_17") (pintype "passive+no_connect"))
    )
    (net (code "95") (name "unconnected-(U1-ADBUS5-Pad18)") (class "Default")
      (node (ref "U1") (pin "18") (pinfunction "ADBUS5_18") (pintype "passive+no_connect"))
    )
    (net (code "96") (name "unconnected-(U1-ADBUS6-Pad19)") (class "Default")
      (node (ref "U1") (pin "19") (pinfunction "ADBUS6_19") (pintype "passive+no_connect"))
    )
    (net (code "97") (name "unconnected-(U1-ADBUS7-Pad20)") (class "Default")
      (node (ref "U1") (pin "20") (pinfunction "ADBUS7_20") (pintype "passive+no_connect"))
    )
    (net (code "98") (name "unconnected-(U1-BCBUS0-Pad42)") (class "Default")
      (node (ref "U1") (pin "42") (pinfunction "BCBUS0_42") (pintype "passive+no_connect"))
    )
    (net (code "99") (name "unconnected-(U1-BCBUS1-Pad46)") (class "Default")
      (node (ref "U1") (pin "46") (pinfunction "BCBUS1_46") (pintype "passive+no_connect"))
    )
    (net (code "100") (name "unconnected-(U1-BCBUS2-Pad47)") (class "Default")
      (node (ref "U1") (pin "47") (pinfunction "BCBUS2_47") (pintype "passive+no_connect"))
    )
    (net (code "101") (name "unconnected-(U1-BCBUS5-Pad51)") (class "Default")
      (node (ref "U1") (pin "51") (pinfunction "BCBUS5_51") (pintype "passive+no_connect"))
    )
    (net (code "102") (name "unconnected-(U1-BCBUS6-Pad52)") (class "Default")
      (node (ref "U1") (pin "52") (pinfunction "BCBUS6_52") (pintype "passive+no_connect"))
    )
    (net (code "103") (name "unconnected-(U1-BDBUS0-Pad32)") (class "Default")
      (node (ref "U1") (pin "32") (pinfunction "BDBUS0_32") (pintype "passive+no_connect"))
    )
    (net (code "104") (name "unconnected-(U1-BDBUS2-Pad34)") (class "Default")
      (node (ref "U1") (pin "34") (pinfunction "BDBUS2_34") (pintype "passive+no_connect"))
    )
    (net (code "105") (name "unconnected-(U1-BDBUS3-Pad35)") (class "Default")
      (node (ref "U1") (pin "35") (pinfunction "BDBUS3_35") (pintype "passive+no_connect"))
    )
    (net (code "106") (name "unconnected-(U1-BDBUS4-Pad37)") (class "Default")
      (node (ref "U1") (pin "37") (pinfunction "BDBUS4_37") (pintype "passive+no_connect"))
    )
    (net (code "107") (name "unconnected-(U1-BDBUS5-Pad38)") (class "Default")
      (node (ref "U1") (pin "38") (pinfunction "BDBUS5_38") (pintype "passive+no_connect"))
    )
    (net (code "108") (name "unconnected-(U1-BDBUS6-Pad39)") (class "Default")
      (node (ref "U1") (pin "39") (pinfunction "BDBUS6_39") (pintype "passive+no_connect"))
    )
    (net (code "109") (name "unconnected-(U1-BDBUS7-Pad40)") (class "Default")
      (node (ref "U1") (pin "40") (pinfunction "BDBUS7_40") (pintype "passive+no_connect"))
    )
    (net (code "110") (name "unconnected-(U1-PWREN#-Pad54)") (class "Default")
      (node (ref "U1") (pin "54") (pinfunction "PWREN#_54") (pintype "passive+no_connect"))
    )
    (net (code "111") (name "unconnected-(U1-SUSPEND#-Pad30)") (class "Default")
      (node (ref "U1") (pin "30") (pinfunction "SUSPEND#_30") (pintype "passive+no_connect"))
    )
  )
)
